# obc-v2_EXP-I2C-IRQ.net
KiCad netlist of a schematic drawn in Altium Designer
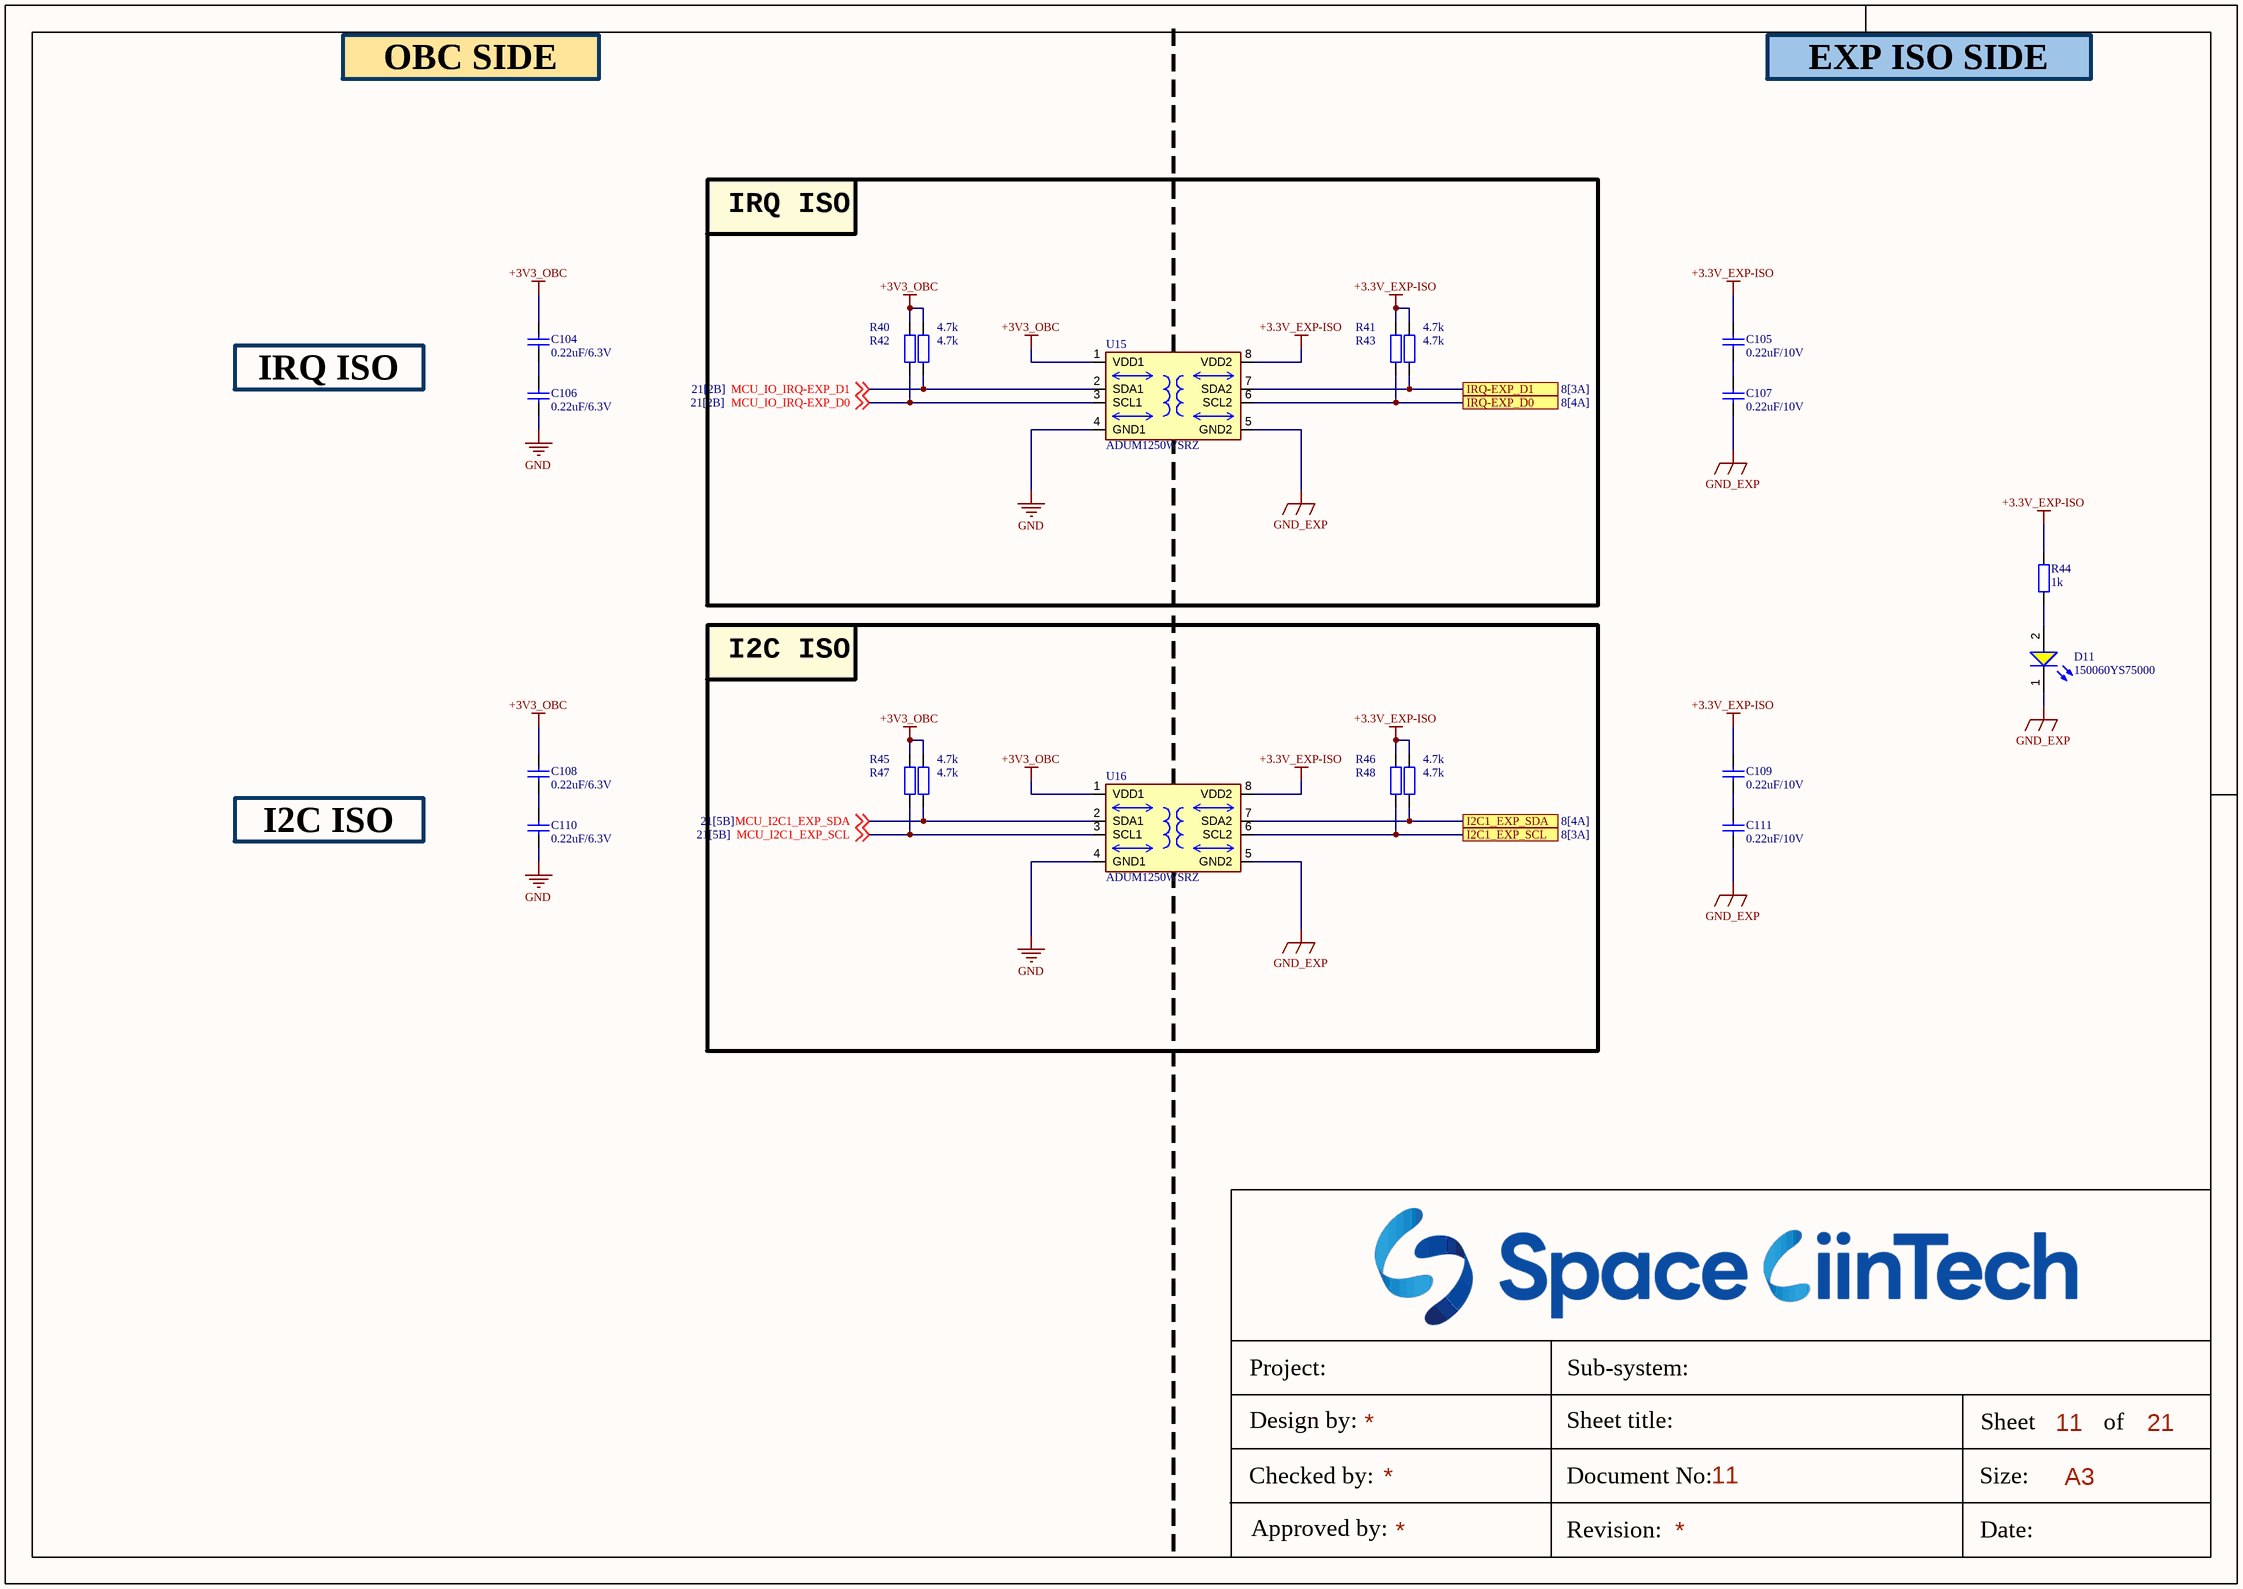
[diagram p0: obc-v2_EXP-I2C-IRQ.SchDoc]

(export (version "E")
  (design (tool "Eeschema 10.0.6"))
  (components
    (comp (ref "C104")
      (value "0.22uF/6.3V")
      (footprint "CAP_C_1005X60")
      (description "CAPC")
      (libsource (lib "Altium_Lib_by_KhueNguyenCreator") (part "Tu 0402 33nF 10V"))
    )
    (comp (ref "C105")
      (value "0.22uF/10V")
      (footprint "CAP_C_1005X60")
      (description "CAPC")
      (libsource (lib "Altium_Lib_by_KhueNguyenCreator") (part "Tu 0402 33nF 10V"))
    )
    (comp (ref "C106")
      (value "0.22uF/6.3V")
      (footprint "CAP_C_1005X60")
      (description "CAPC")
      (libsource (lib "Altium_Lib_by_KhueNguyenCreator") (part "Tu 0402 33nF 10V"))
    )
    (comp (ref "C107")
      (value "0.22uF/10V")
      (footprint "CAP_C_1005X60")
      (description "CAPC")
      (libsource (lib "Altium_Lib_by_KhueNguyenCreator") (part "Tu 0402 33nF 10V"))
    )
    (comp (ref "C108")
      (value "0.22uF/6.3V")
      (footprint "CAP_C_1005X60")
      (description "CAPC")
      (libsource (lib "Altium_Lib_by_KhueNguyenCreator") (part "Tu 0402 33nF 10V"))
    )
    (comp (ref "C109")
      (value "0.22uF/10V")
      (footprint "CAP_C_1005X60")
      (description "CAPC")
      (libsource (lib "Altium_Lib_by_KhueNguyenCreator") (part "Tu 0402 33nF 10V"))
    )
    (comp (ref "C110")
      (value "0.22uF/6.3V")
      (footprint "CAP_C_1005X60")
      (description "CAPC")
      (libsource (lib "Altium_Lib_by_KhueNguyenCreator") (part "Tu 0402 33nF 10V"))
    )
    (comp (ref "C111")
      (value "0.22uF/10V")
      (footprint "CAP_C_1005X60")
      (description "CAPC")
      (libsource (lib "Altium_Lib_by_KhueNguyenCreator") (part "Tu 0402 33nF 10V"))
    )
    (comp (ref "D11")
      (value "150060YS75000")
      (footprint "WL-SMCW_0603_150060xx75000")
      (description "LED YELLOW CLEAR 0603 SMD")
      (libsource (lib "Altium Content Vault") (part "LED_Yellow_2A-1K"))
    )
    (comp (ref "R40")
      (value "4.7k")
      (footprint "RES_C_1608X60")
      (description "RES")
      (libsource (lib "Altium_Lib_by_KhueNguyenCreator") (part "Tro 0603 1% 10k"))
    )
    (comp (ref "R41")
      (value "4.7k")
      (footprint "RES_C_1608X60")
      (description "RES")
      (libsource (lib "Altium_Lib_by_KhueNguyenCreator") (part "Tro 0603 1% 10k"))
    )
    (comp (ref "R42")
      (value "4.7k")
      (footprint "RES_C_1608X60")
      (description "RES")
      (libsource (lib "Altium_Lib_by_KhueNguyenCreator") (part "Tro 0603 1% 10k"))
    )
    (comp (ref "R43")
      (value "4.7k")
      (footprint "RES_C_1608X60")
      (description "RES")
      (libsource (lib "Altium_Lib_by_KhueNguyenCreator") (part "Tro 0603 1% 10k"))
    )
    (comp (ref "R44")
      (value "1k")
      (footprint "RES_C_1608X60")
      (description "RES")
      (libsource (lib "Altium_Lib_by_KhueNguyenCreator") (part "Tro 0603 1% 10k"))
    )
    (comp (ref "R45")
      (value "4.7k")
      (footprint "RES_C_1608X60")
      (description "RES")
      (libsource (lib "Altium_Lib_by_KhueNguyenCreator") (part "Tro 0603 1% 10k"))
    )
    (comp (ref "R46")
      (value "4.7k")
      (footprint "RES_C_1608X60")
      (description "RES")
      (libsource (lib "Altium_Lib_by_KhueNguyenCreator") (part "Tro 0603 1% 10k"))
    )
    (comp (ref "R47")
      (value "4.7k")
      (footprint "RES_C_1608X60")
      (description "RES")
      (libsource (lib "Altium_Lib_by_KhueNguyenCreator") (part "Tro 0603 1% 10k"))
    )
    (comp (ref "R48")
      (value "4.7k")
      (footprint "RES_C_1608X60")
      (description "RES")
      (libsource (lib "Altium_Lib_by_KhueNguyenCreator") (part "Tro 0603 1% 10k"))
    )
    (comp (ref "U15")
      (value "ADUM1250WSRZ")
      (footprint "SOIC127P602X173-8N")
      (description "I虏C Digital Isolator 2500Vrms 2 Channel 1Mbps 25kV/碌s CMTI 8-SOIC (0.154\", 3.90mm Width)")
      (fields (field (name "MF") "Analog Devices") (field (name "MP") "ADUM1250"))
      (libsource (lib "ADUM1250") (part "ADUM1250"))
    )
    (comp (ref "U16")
      (value "ADUM1250WSRZ")
      (footprint "SOIC127P602X173-8N")
      (description "I虏C Digital Isolator 2500Vrms 2 Channel 1Mbps 25kV/碌s CMTI 8-SOIC (0.154\", 3.90mm Width)")
      (fields (field (name "MF") "Analog Devices") (field (name "MP") "ADUM1250"))
      (libsource (lib "ADUM1250") (part "ADUM1250"))
    )
  )
  (nets
    (net (code "1") (name "+3.3V_EXP-ISO") (class "Default")
      (node (ref "C105") (pin "1") (pinfunction "1_1") (pintype "passive"))
      (node (ref "C109") (pin "1") (pinfunction "1_1") (pintype "passive"))
      (node (ref "R41") (pin "2") (pinfunction "2_2") (pintype "passive"))
      (node (ref "R43") (pin "2") (pinfunction "2_2") (pintype "passive"))
      (node (ref "R44") (pin "2") (pinfunction "2_2") (pintype "passive"))
      (node (ref "R46") (pin "2") (pinfunction "2_2") (pintype "passive"))
      (node (ref "R48") (pin "2") (pinfunction "2_2") (pintype "passive"))
      (node (ref "U15") (pin "8") (pinfunction "VDD2_8") (pintype "power_in"))
      (node (ref "U16") (pin "8") (pinfunction "VDD2_8") (pintype "power_in"))
    )
    (net (code "2") (name "+3V3_OBC") (class "Default")
      (node (ref "C104") (pin "1") (pinfunction "1_1") (pintype "passive"))
      (node (ref "C108") (pin "1") (pinfunction "1_1") (pintype "passive"))
      (node (ref "R40") (pin "2") (pinfunction "2_2") (pintype "passive"))
      (node (ref "R42") (pin "2") (pinfunction "2_2") (pintype "passive"))
      (node (ref "R45") (pin "2") (pinfunction "2_2") (pintype "passive"))
      (node (ref "R47") (pin "2") (pinfunction "2_2") (pintype "passive"))
      (node (ref "U15") (pin "1") (pinfunction "VDD1_1") (pintype "power_in"))
      (node (ref "U16") (pin "1") (pinfunction "VDD1_1") (pintype "power_in"))
    )
    (net (code "3") (name "/I2C1_EXP_SCL") (class "Default")
      (node (ref "R46") (pin "1") (pinfunction "1_1") (pintype "passive"))
      (node (ref "U16") (pin "6") (pinfunction "SCL2_6") (pintype "bidirectional"))
    )
    (net (code "4") (name "/I2C1_EXP_SDA") (class "Default")
      (node (ref "R48") (pin "1") (pinfunction "1_1") (pintype "passive"))
      (node (ref "U16") (pin "7") (pinfunction "SDA2_7") (pintype "bidirectional"))
    )
    (net (code "5") (name "/IRQ-EXP_D0") (class "Default")
      (node (ref "R41") (pin "1") (pinfunction "1_1") (pintype "passive"))
      (node (ref "U15") (pin "6") (pinfunction "SCL2_6") (pintype "bidirectional"))
    )
    (net (code "6") (name "/IRQ-EXP_D1") (class "Default")
      (node (ref "R43") (pin "1") (pinfunction "1_1") (pintype "passive"))
      (node (ref "U15") (pin "7") (pinfunction "SDA2_7") (pintype "bidirectional"))
    )
    (net (code "7") (name "GND") (class "Default")
      (node (ref "C106") (pin "2") (pinfunction "2_2") (pintype "passive"))
      (node (ref "C110") (pin "2") (pinfunction "2_2") (pintype "passive"))
      (node (ref "U15") (pin "4") (pinfunction "GND1_4") (pintype "power_in"))
      (node (ref "U16") (pin "4") (pinfunction "GND1_4") (pintype "power_in"))
    )
    (net (code "8") (name "GND_EXP") (class "Default")
      (node (ref "C107") (pin "2") (pinfunction "2_2") (pintype "passive"))
      (node (ref "C111") (pin "2") (pinfunction "2_2") (pintype "passive"))
      (node (ref "D11") (pin "1") (pinfunction "K_1") (pintype "passive"))
      (node (ref "U15") (pin "5") (pinfunction "GND2_5") (pintype "power_in"))
      (node (ref "U16") (pin "5") (pinfunction "GND2_5") (pintype "power_in"))
    )
    (net (code "9") (name "MCU_I2C1_EXP_SCL") (class "Default")
      (node (ref "R45") (pin "1") (pinfunction "1_1") (pintype "passive"))
      (node (ref "U16") (pin "3") (pinfunction "SCL1_3") (pintype "bidirectional"))
    )
    (net (code "10") (name "MCU_I2C1_EXP_SDA") (class "Default")
      (node (ref "R47") (pin "1") (pinfunction "1_1") (pintype "passive"))
      (node (ref "U16") (pin "2") (pinfunction "SDA1_2") (pintype "bidirectional"))
    )
    (net (code "11") (name "MCU_IO_IRQ-EXP_D0") (class "Default")
      (node (ref "R40") (pin "1") (pinfunction "1_1") (pintype "passive"))
      (node (ref "U15") (pin "3") (pinfunction "SCL1_3") (pintype "bidirectional"))
    )
    (net (code "12") (name "MCU_IO_IRQ-EXP_D1") (class "Default")
      (node (ref "R42") (pin "1") (pinfunction "1_1") (pintype "passive"))
      (node (ref "U15") (pin "2") (pinfunction "SDA1_2") (pintype "bidirectional"))
    )
    (net (code "13") (name "Net-(C104-Pad2)") (class "Default")
      (node (ref "C104") (pin "2") (pinfunction "2_2") (pintype "passive"))
      (node (ref "C106") (pin "1") (pinfunction "1_1") (pintype "passive"))
    )
    (net (code "14") (name "Net-(C105-Pad2)") (class "Default")
      (node (ref "C105") (pin "2") (pinfunction "2_2") (pintype "passive"))
      (node (ref "C107") (pin "1") (pinfunction "1_1") (pintype "passive"))
    )
    (net (code "15") (name "Net-(C108-Pad2)") (class "Default")
      (node (ref "C108") (pin "2") (pinfunction "2_2") (pintype "passive"))
      (node (ref "C110") (pin "1") (pinfunction "1_1") (pintype "passive"))
    )
    (net (code "16") (name "Net-(C109-Pad2)") (class "Default")
      (node (ref "C109") (pin "2") (pinfunction "2_2") (pintype "passive"))
      (node (ref "C111") (pin "1") (pinfunction "1_1") (pintype "passive"))
    )
    (net (code "17") (name "Net-(D11-A)") (class "Default")
      (node (ref "D11") (pin "2") (pinfunction "A_2") (pintype "passive"))
      (node (ref "R44") (pin "1") (pinfunction "1_1") (pintype "passive"))
    )
  )
)
